# pecoskiSmartWatch-BASIC-TOP.net
KiCad netlist of a schematic drawn in EAGLE
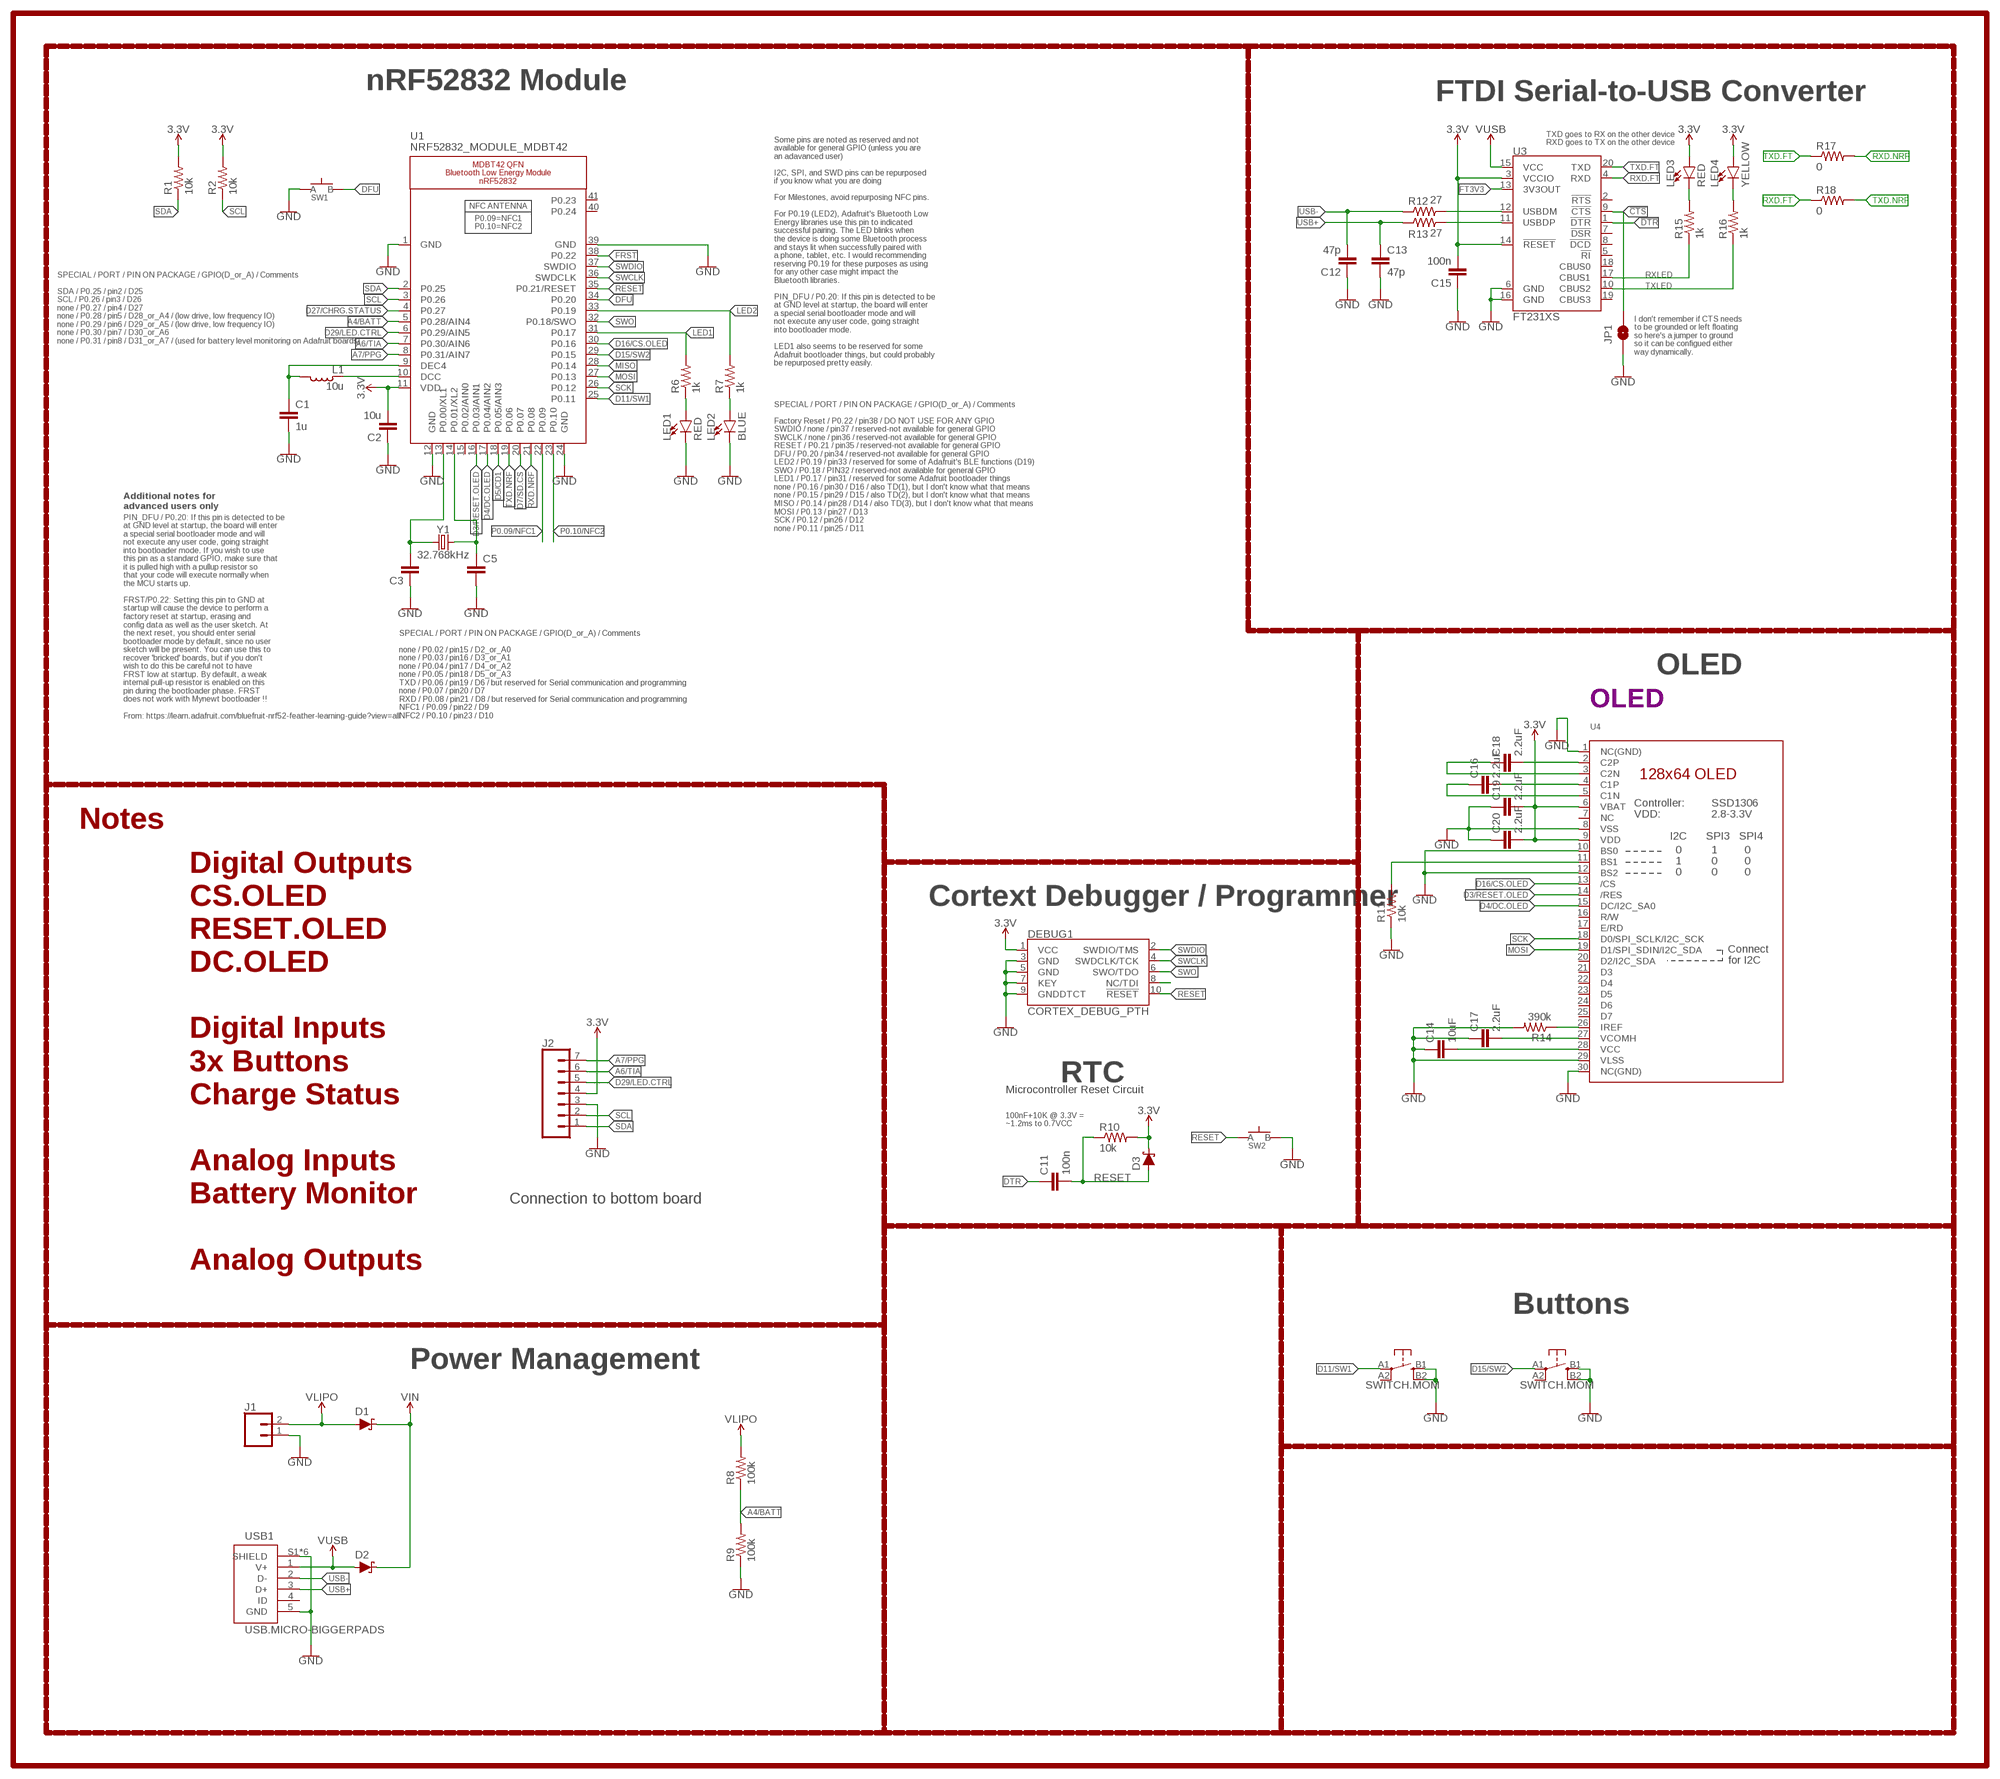
[diagram p0: schematic, sheet 1]

(export (version "E")
  (design (tool "Eeschema 10.0.6"))
  (components
    (comp (ref "C1")
      (value "1u")
      (footprint "eagle-import:C0603")
      (libsource (lib "eagle-import") (part "CAPACITOR0603"))
    )
    (comp (ref "C2")
      (value "10u")
      (footprint "eagle-import:C0805")
      (libsource (lib "eagle-import") (part "CAPACITOR0805"))
    )
    (comp (ref "C3")
      (value "CAPACITOR0603")
      (footprint "eagle-import:C0603")
      (libsource (lib "eagle-import") (part "CAPACITOR0603"))
    )
    (comp (ref "C5")
      (value "CAPACITOR0603")
      (footprint "eagle-import:C0603")
      (libsource (lib "eagle-import") (part "CAPACITOR0603"))
    )
    (comp (ref "C11")
      (value "100n")
      (footprint "eagle-import:C0603")
      (libsource (lib "eagle-import") (part "CAPACITOR0603"))
    )
    (comp (ref "C12")
      (value "47p")
      (footprint "eagle-import:C0603")
      (libsource (lib "eagle-import") (part "CAPACITOR0603"))
    )
    (comp (ref "C13")
      (value "47p")
      (footprint "eagle-import:C0603")
      (libsource (lib "eagle-import") (part "CAPACITOR0603"))
    )
    (comp (ref "C14")
      (value "10uF")
      (footprint "eagle-import:C0603")
      (libsource (lib "eagle-import") (part "CAPACITOR0603"))
    )
    (comp (ref "C15")
      (value "100n")
      (footprint "eagle-import:C0603")
      (libsource (lib "eagle-import") (part "CAPACITOR0603"))
    )
    (comp (ref "C16")
      (value "2.2uF")
      (footprint "eagle-import:C0402")
      (libsource (lib "eagle-import") (part "CAPACITOR0402"))
    )
    (comp (ref "C17")
      (value "2.2uF")
      (footprint "eagle-import:C0402")
      (libsource (lib "eagle-import") (part "CAPACITOR0402"))
    )
    (comp (ref "C18")
      (value "2.2uF")
      (footprint "eagle-import:C0402")
      (libsource (lib "eagle-import") (part "CAPACITOR0402"))
    )
    (comp (ref "C19")
      (value "2.2uF")
      (footprint "eagle-import:C0402")
      (libsource (lib "eagle-import") (part "CAPACITOR0402"))
    )
    (comp (ref "C20")
      (value "2.2uF")
      (footprint "eagle-import:C0402")
      (libsource (lib "eagle-import") (part "CAPACITOR0402"))
    )
    (comp (ref "D1")
      (value "SCHOTTKY-USC")
      (footprint "eagle-import:USC")
      (libsource (lib "eagle-import") (part "SCHOTTKY-USC"))
    )
    (comp (ref "D2")
      (value "SCHOTTKY-USC")
      (footprint "eagle-import:USC")
      (libsource (lib "eagle-import") (part "SCHOTTKY-USC"))
    )
    (comp (ref "D3")
      (value "SCHOTTKY-USC")
      (footprint "eagle-import:USC")
      (libsource (lib "eagle-import") (part "SCHOTTKY-USC"))
    )
    (comp (ref "DEBUG1")
      (value "CORTEX_DEBUG_PTH")
      (footprint "eagle-import:2X5-PTH-1.27MM")
      (libsource (lib "eagle-import") (part "CORTEX_DEBUG_PTH"))
    )
    (comp (ref "J1")
      (value "CONN_02")
      (footprint "eagle-import:1X02")
      (libsource (lib "eagle-import") (part "CONN_02"))
    )
    (comp (ref "J2")
      (value "CONN_07-1.27MM")
      (footprint "eagle-import:1X07_1.27MM")
      (libsource (lib "eagle-import") (part "CONN_07-1.27MM"))
    )
    (comp (ref "JP1")
      (value "JUMPER-SMT_2_NO_SILK")
      (footprint "eagle-import:SMT-JUMPER_2_NO_SILK")
      (libsource (lib "eagle-import") (part "JUMPER-SMT_2_NO_SILK"))
    )
    (comp (ref "L1")
      (value "10u")
      (footprint "eagle-import:L0603")
      (libsource (lib "eagle-import") (part "INDUCTOR0603"))
    )
    (comp (ref "LED1")
      (value "RED")
      (footprint "eagle-import:LED-0603")
      (libsource (lib "eagle-import") (part "LED0603"))
    )
    (comp (ref "LED2")
      (value "BLUE")
      (footprint "eagle-import:LED-0603")
      (libsource (lib "eagle-import") (part "LED0603"))
    )
    (comp (ref "LED3")
      (value "RED")
      (footprint "eagle-import:LED-0603")
      (libsource (lib "eagle-import") (part "LED0603"))
    )
    (comp (ref "LED4")
      (value "YELLOW")
      (footprint "eagle-import:LED-0603")
      (libsource (lib "eagle-import") (part "LED0603"))
    )
    (comp (ref "R1")
      (value "10k")
      (footprint "eagle-import:R0603")
      (libsource (lib "eagle-import") (part "RESISTOR0603"))
    )
    (comp (ref "R2")
      (value "10k")
      (footprint "eagle-import:R0603")
      (libsource (lib "eagle-import") (part "RESISTOR0603"))
    )
    (comp (ref "R6")
      (value "1k")
      (footprint "eagle-import:R0603")
      (libsource (lib "eagle-import") (part "RESISTOR0603"))
    )
    (comp (ref "R7")
      (value "1k")
      (footprint "eagle-import:R0603")
      (libsource (lib "eagle-import") (part "RESISTOR0603"))
    )
    (comp (ref "R8")
      (value "100k")
      (footprint "eagle-import:R0603")
      (libsource (lib "eagle-import") (part "RESISTOR0603"))
    )
    (comp (ref "R9")
      (value "100k")
      (footprint "eagle-import:R0603")
      (libsource (lib "eagle-import") (part "RESISTOR0603"))
    )
    (comp (ref "R10")
      (value "10k")
      (footprint "eagle-import:R0603")
      (libsource (lib "eagle-import") (part "RESISTOR0603"))
    )
    (comp (ref "R11")
      (value "10k")
      (footprint "eagle-import:R0603")
      (libsource (lib "eagle-import") (part "RESISTOR0603"))
    )
    (comp (ref "R12")
      (value "27")
      (footprint "eagle-import:R0603")
      (libsource (lib "eagle-import") (part "RESISTOR0603"))
    )
    (comp (ref "R13")
      (value "27")
      (footprint "eagle-import:R0603")
      (libsource (lib "eagle-import") (part "RESISTOR0603"))
    )
    (comp (ref "R14")
      (value "390k")
      (footprint "eagle-import:R0603")
      (libsource (lib "eagle-import") (part "RESISTOR0603"))
    )
    (comp (ref "R15")
      (value "1k")
      (footprint "eagle-import:R0603")
      (libsource (lib "eagle-import") (part "RESISTOR0603"))
    )
    (comp (ref "R16")
      (value "1k")
      (footprint "eagle-import:R0603")
      (libsource (lib "eagle-import") (part "RESISTOR0603"))
    )
    (comp (ref "R17")
      (value "0")
      (footprint "eagle-import:R0603")
      (libsource (lib "eagle-import") (part "RESISTOR0603"))
    )
    (comp (ref "R18")
      (value "0")
      (footprint "eagle-import:R0603")
      (libsource (lib "eagle-import") (part "RESISTOR0603"))
    )
    (comp (ref "SW1")
      (value "SPST-PTS830GG140-COPY.1-3")
      (footprint "eagle-import:BUTTON-GULLWING")
      (libsource (lib "eagle-import") (part "SPST-PTS830GG140-COPY.1-3"))
    )
    (comp (ref "SW2")
      (value "SPST-PTS830GG140-COPY.1-3")
      (footprint "eagle-import:BUTTON-GULLWING")
      (libsource (lib "eagle-import") (part "SPST-PTS830GG140-COPY.1-3"))
    )
    (comp (ref "SW3")
      (value "SWITCH.MOM")
      (footprint "eagle-import:TACTILE_SWITCH_SMD_6.2MM_TALL")
      (libsource (lib "eagle-import") (part "SWITCH.MOM"))
    )
    (comp (ref "SW4")
      (value "SWITCH.MOM")
      (footprint "eagle-import:TACTILE_SWITCH_SMD_6.2MM_TALL")
      (libsource (lib "eagle-import") (part "SWITCH.MOM"))
    )
    (comp (ref "U1")
      (value "NRF52832_MODULE_MDBT42")
      (footprint "eagle-import:BLE_MODULE_RAYTAC_MDBT42")
      (libsource (lib "eagle-import") (part "NRF52832_MODULE_MDBT42"))
    )
    (comp (ref "U3")
      (value "FT231XS")
      (footprint "eagle-import:SSOP20_L")
      (libsource (lib "eagle-import") (part "FT231XS"))
    )
    (comp (ref "U4")
      (value "DISP_OLED_UG-2864HSWEG01-NO-WRAPAROUND")
      (footprint "eagle-import:UG-2864HSWEG01_0.96IN_NO-WRAPAROUND")
      (libsource (lib "eagle-import") (part "DISP_OLED_UG-2864HSWEG01-NO-WRAPAROUND"))
    )
    (comp (ref "USB1")
      (value "USB.MICRO-BIGGERPADS")
      (footprint "eagle-import:USB-MICRO-01.BIGGERPADS")
      (libsource (lib "eagle-import") (part "USB.MICRO-BIGGERPADS"))
    )
    (comp (ref "Y1")
      (value "32.768kHz")
      (footprint "eagle-import:2-SMD.NOLEAD.2.0MMTO1.2MM")
      (libsource (lib "eagle-import") (part "CRYSTALECS-.327-12.5-12-C-TR"))
    )
  )
  (nets
    (net (code "1") (name "/RXLED") (class "Default")
      (node (ref "R15") (pin "1") (pinfunction "1_1") (pintype "passive"))
      (node (ref "U3") (pin "17") (pinfunction "CBUS1_17") (pintype "bidirectional"))
    )
    (net (code "2") (name "/TXLED") (class "Default")
      (node (ref "R16") (pin "1") (pinfunction "1_1") (pintype "passive"))
      (node (ref "U3") (pin "10") (pinfunction "CBUS2_10") (pintype "bidirectional"))
    )
    (net (code "3") (name "/~{CTS}") (class "Default")
      (node (ref "JP1") (pin "2") (pinfunction "2_2") (pintype "passive"))
      (node (ref "U3") (pin "9") (pinfunction "~{CTS}_9") (pintype "bidirectional"))
    )
    (net (code "4") (name "/~{DTR}") (class "Default")
      (node (ref "U3") (pin "1") (pinfunction "~{DTR}_1") (pintype "bidirectional"))
    )
    (net (code "5") (name "3.3V") (class "Default")
      (node (ref "C15") (pin "2") (pinfunction "2_2") (pintype "passive"))
      (node (ref "C19") (pin "2") (pinfunction "2_2") (pintype "passive"))
      (node (ref "C2") (pin "2") (pinfunction "2_2") (pintype "passive"))
      (node (ref "C20") (pin "2") (pinfunction "2_2") (pintype "passive"))
      (node (ref "D3") (pin "-") (pinfunction "C_-") (pintype "passive"))
      (node (ref "DEBUG1") (pin "1") (pinfunction "VCC_1") (pintype "bidirectional"))
      (node (ref "J2") (pin "4") (pinfunction "4_4") (pintype "passive"))
      (node (ref "LED3") (pin "A") (pinfunction "A_A") (pintype "passive"))
      (node (ref "LED4") (pin "A") (pinfunction "A_A") (pintype "passive"))
      (node (ref "R1") (pin "2") (pinfunction "2_2") (pintype "passive"))
      (node (ref "R10") (pin "2") (pinfunction "2_2") (pintype "passive"))
      (node (ref "R2") (pin "2") (pinfunction "2_2") (pintype "passive"))
      (node (ref "U1") (pin "11") (pinfunction "VDD_11") (pintype "bidirectional"))
      (node (ref "U3") (pin "14") (pinfunction "~{RESET}_14") (pintype "bidirectional"))
      (node (ref "U3") (pin "3") (pinfunction "VCCIO_3") (pintype "bidirectional"))
      (node (ref "U4") (pin "6") (pinfunction "VBAT_6") (pintype "input"))
      (node (ref "U4") (pin "9") (pinfunction "VDD_9") (pintype "power_in"))
    )
    (net (code "6") (name "A4{slash}BATT") (class "Default")
      (node (ref "R8") (pin "1") (pinfunction "1_1") (pintype "passive"))
      (node (ref "R9") (pin "2") (pinfunction "2_2") (pintype "passive"))
      (node (ref "U1") (pin "5") (pinfunction "P0.28/AIN4_5") (pintype "bidirectional"))
    )
    (net (code "7") (name "A6{slash}TIA") (class "Default")
      (node (ref "J2") (pin "6") (pinfunction "6_6") (pintype "passive"))
      (node (ref "U1") (pin "7") (pinfunction "P0.30/AIN6_7") (pintype "bidirectional"))
    )
    (net (code "8") (name "A7{slash}PPG") (class "Default")
      (node (ref "J2") (pin "7") (pinfunction "7_7") (pintype "passive"))
      (node (ref "U1") (pin "8") (pinfunction "P0.31/AIN7_8") (pintype "bidirectional"))
    )
    (net (code "9") (name "D3{slash}RESET.OLED") (class "Default")
      (node (ref "U1") (pin "16") (pinfunction "P0.03/AIN1_16") (pintype "bidirectional"))
      (node (ref "U4") (pin "14") (pinfunction "/RES_14") (pintype "input"))
    )
    (net (code "10") (name "D4{slash}DC.OLED") (class "Default")
      (node (ref "U1") (pin "17") (pinfunction "P0.04/AIN2_17") (pintype "bidirectional"))
      (node (ref "U4") (pin "15") (pinfunction "DC/I2C_SA0_15") (pintype "input"))
    )
    (net (code "11") (name "D5{slash}CD1") (class "Default")
      (node (ref "U1") (pin "18") (pinfunction "P0.05/AIN3_18") (pintype "bidirectional"))
    )
    (net (code "12") (name "D7{slash}SD.CS") (class "Default")
      (node (ref "U1") (pin "20") (pinfunction "P0.07_20") (pintype "bidirectional"))
    )
    (net (code "13") (name "D11{slash}SW1") (class "Default")
      (node (ref "SW3") (pin "A1") (pinfunction "1_A1") (pintype "passive"))
      (node (ref "U1") (pin "25") (pinfunction "P0.11_25") (pintype "bidirectional"))
    )
    (net (code "14") (name "D15{slash}SW2") (class "Default")
      (node (ref "SW4") (pin "A1") (pinfunction "1_A1") (pintype "passive"))
      (node (ref "U1") (pin "29") (pinfunction "P0.15_29") (pintype "bidirectional"))
    )
    (net (code "15") (name "D16{slash}CS.OLED") (class "Default")
      (node (ref "U1") (pin "30") (pinfunction "P0.16_30") (pintype "bidirectional"))
      (node (ref "U4") (pin "13") (pinfunction "/CS_13") (pintype "input"))
    )
    (net (code "16") (name "D27{slash}CHRG.STATUS") (class "Default")
      (node (ref "U1") (pin "4") (pinfunction "P0.27_4") (pintype "bidirectional"))
    )
    (net (code "17") (name "D29{slash}LED.CTRL") (class "Default")
      (node (ref "J2") (pin "5") (pinfunction "5_5") (pintype "passive"))
      (node (ref "U1") (pin "6") (pinfunction "P0.29/AIN5_6") (pintype "bidirectional"))
    )
    (net (code "18") (name "DFU") (class "Default")
      (node (ref "SW1") (pin "3") (pinfunction "B_3") (pintype "bidirectional"))
      (node (ref "U1") (pin "34") (pinfunction "P0.20_34") (pintype "bidirectional"))
    )
    (net (code "19") (name "DTR") (class "Default")
      (node (ref "C11") (pin "1") (pinfunction "1_1") (pintype "passive"))
    )
    (net (code "20") (name "FRST") (class "Default")
      (node (ref "U1") (pin "38") (pinfunction "P0.22_38") (pintype "bidirectional"))
    )
    (net (code "21") (name "FT3V3") (class "Default")
      (node (ref "U3") (pin "13") (pinfunction "3V3OUT_13") (pintype "bidirectional"))
    )
    (net (code "22") (name "GND") (class "Default")
      (node (ref "C1") (pin "2") (pinfunction "2_2") (pintype "passive"))
      (node (ref "C12") (pin "1") (pinfunction "1_1") (pintype "passive"))
      (node (ref "C13") (pin "2") (pinfunction "2_2") (pintype "passive"))
      (node (ref "C14") (pin "1") (pinfunction "1_1") (pintype "passive"))
      (node (ref "C15") (pin "1") (pinfunction "1_1") (pintype "passive"))
      (node (ref "C17") (pin "1") (pinfunction "1_1") (pintype "passive"))
      (node (ref "C19") (pin "1") (pinfunction "1_1") (pintype "passive"))
      (node (ref "C2") (pin "1") (pinfunction "1_1") (pintype "passive"))
      (node (ref "C20") (pin "1") (pinfunction "1_1") (pintype "passive"))
      (node (ref "C3") (pin "1") (pinfunction "1_1") (pintype "passive"))
      (node (ref "C5") (pin "2") (pinfunction "2_2") (pintype "passive"))
      (node (ref "DEBUG1") (pin "3") (pinfunction "GND_3") (pintype "bidirectional"))
      (node (ref "DEBUG1") (pin "5") (pinfunction "GND_5") (pintype "bidirectional"))
      (node (ref "DEBUG1") (pin "7") (pinfunction "KEY_7") (pintype "bidirectional"))
      (node (ref "DEBUG1") (pin "9") (pinfunction "GNDDTCT_9") (pintype "bidirectional"))
      (node (ref "J1") (pin "1") (pinfunction "1_1") (pintype "passive"))
      (node (ref "J2") (pin "3") (pinfunction "3_3") (pintype "passive"))
      (node (ref "JP1") (pin "1") (pinfunction "1_1") (pintype "passive"))
      (node (ref "LED1") (pin "C") (pinfunction "C_C") (pintype "passive"))
      (node (ref "LED2") (pin "C") (pinfunction "C_C") (pintype "passive"))
      (node (ref "R11") (pin "1") (pinfunction "1_1") (pintype "passive"))
      (node (ref "R14") (pin "2") (pinfunction "2_2") (pintype "passive"))
      (node (ref "R9") (pin "1") (pinfunction "1_1") (pintype "passive"))
      (node (ref "SW1") (pin "1") (pinfunction "A_1") (pintype "bidirectional"))
      (node (ref "SW2") (pin "3") (pinfunction "B_3") (pintype "bidirectional"))
      (node (ref "SW3") (pin "B1") (pinfunction "3_B1") (pintype "passive"))
      (node (ref "SW3") (pin "B2") (pinfunction "4_B2") (pintype "passive"))
      (node (ref "SW4") (pin "B1") (pinfunction "3_B1") (pintype "passive"))
      (node (ref "SW4") (pin "B2") (pinfunction "4_B2") (pintype "passive"))
      (node (ref "U1") (pin "1") (pinfunction "GND_1") (pintype "bidirectional"))
      (node (ref "U1") (pin "12") (pinfunction "GND_12") (pintype "bidirectional"))
      (node (ref "U1") (pin "24") (pinfunction "GND_24") (pintype "bidirectional"))
      (node (ref "U1") (pin "39") (pinfunction "GND_39") (pintype "bidirectional"))
      (node (ref "U3") (pin "16") (pinfunction "GND_16") (pintype "bidirectional"))
      (node (ref "U3") (pin "6") (pinfunction "GND_6") (pintype "bidirectional"))
      (node (ref "U4") (pin "1") (pinfunction "NC(GND)_1") (pintype "input"))
      (node (ref "U4") (pin "10") (pinfunction "BS0_10") (pintype "input"))
      (node (ref "U4") (pin "12") (pinfunction "BS2_12") (pintype "input"))
      (node (ref "U4") (pin "29") (pinfunction "VLSS_29") (pintype "power_in"))
      (node (ref "U4") (pin "30") (pinfunction "NC(GND)_30") (pintype "input"))
      (node (ref "U4") (pin "8") (pinfunction "VSS_8") (pintype "power_in"))
      (node (ref "USB1") (pin "5") (pinfunction "GND_5") (pintype "bidirectional"))
      (node (ref "USB1") (pin "S1") (pinfunction "SHIELD_S1") (pintype "bidirectional"))
      (node (ref "USB1") (pin "S2") (pinfunction "SHIELD_S2") (pintype "bidirectional"))
      (node (ref "USB1") (pin "S3") (pinfunction "SHIELD_S3") (pintype "bidirectional"))
      (node (ref "USB1") (pin "S4") (pinfunction "SHIELD_S4") (pintype "bidirectional"))
      (node (ref "USB1") (pin "S5") (pinfunction "SHIELD_S5") (pintype "bidirectional"))
      (node (ref "USB1") (pin "S6") (pinfunction "SHIELD_S6") (pintype "bidirectional"))
    )
    (net (code "23") (name "LED1") (class "Default")
      (node (ref "R6") (pin "2") (pinfunction "2_2") (pintype "passive"))
      (node (ref "U1") (pin "31") (pinfunction "P0.17_31") (pintype "bidirectional"))
    )
    (net (code "24") (name "LED2") (class "Default")
      (node (ref "R7") (pin "2") (pinfunction "2_2") (pintype "passive"))
      (node (ref "U1") (pin "33") (pinfunction "P0.19_33") (pintype "bidirectional"))
    )
    (net (code "25") (name "MISO") (class "Default")
      (node (ref "U1") (pin "28") (pinfunction "P0.14_28") (pintype "bidirectional"))
    )
    (net (code "26") (name "MOSI") (class "Default")
      (node (ref "U1") (pin "27") (pinfunction "P0.13_27") (pintype "bidirectional"))
      (node (ref "U4") (pin "19") (pinfunction "D1/SPI_SDIN/I2C_SDA_19") (pintype "bidirectional"))
    )
    (net (code "27") (name "Net-(LED1-PadA)") (class "Default")
      (node (ref "LED1") (pin "A") (pinfunction "A_A") (pintype "passive"))
      (node (ref "R6") (pin "1") (pinfunction "1_1") (pintype "passive"))
    )
    (net (code "28") (name "Net-(LED2-PadA)") (class "Default")
      (node (ref "LED2") (pin "A") (pinfunction "A_A") (pintype "passive"))
      (node (ref "R7") (pin "1") (pinfunction "1_1") (pintype "passive"))
    )
    (net (code "29") (name "Net-(LED3-PadC)") (class "Default")
      (node (ref "LED3") (pin "C") (pinfunction "C_C") (pintype "passive"))
      (node (ref "R15") (pin "2") (pinfunction "2_2") (pintype "passive"))
    )
    (net (code "30") (name "Net-(LED4-PadC)") (class "Default")
      (node (ref "LED4") (pin "C") (pinfunction "C_C") (pintype "passive"))
      (node (ref "R16") (pin "2") (pinfunction "2_2") (pintype "passive"))
    )
    (net (code "31") (name "Net-(U1-DCC)") (class "Default")
      (node (ref "L1") (pin "1") (pinfunction "1_1") (pintype "passive"))
      (node (ref "U1") (pin "10") (pinfunction "DCC_10") (pintype "bidirectional"))
    )
    (net (code "32") (name "Net-(U1-DEC4)") (class "Default")
      (node (ref "C1") (pin "1") (pinfunction "1_1") (pintype "passive"))
      (node (ref "L1") (pin "2") (pinfunction "2_2") (pintype "passive"))
      (node (ref "U1") (pin "9") (pinfunction "DEC4_9") (pintype "bidirectional"))
    )
    (net (code "33") (name "Net-(U1-P0.00{slash}XL1)") (class "Default")
      (node (ref "C3") (pin "2") (pinfunction "2_2") (pintype "passive"))
      (node (ref "U1") (pin "13") (pinfunction "P0.00/XL1_13") (pintype "bidirectional"))
      (node (ref "Y1") (pin "P$1") (pinfunction "1_P$1") (pintype "passive"))
    )
    (net (code "34") (name "Net-(U1-P0.01{slash}XL2)") (class "Default")
      (node (ref "C5") (pin "1") (pinfunction "1_1") (pintype "passive"))
      (node (ref "U1") (pin "14") (pinfunction "P0.01/XL2_14") (pintype "bidirectional"))
      (node (ref "Y1") (pin "P$2") (pinfunction "2_P$2") (pintype "passive"))
    )
    (net (code "35") (name "Net-(U3-USBDM)") (class "Default")
      (node (ref "R12") (pin "2") (pinfunction "2_2") (pintype "passive"))
      (node (ref "U3") (pin "12") (pinfunction "USBDM_12") (pintype "bidirectional"))
    )
    (net (code "36") (name "Net-(U3-USBDP)") (class "Default")
      (node (ref "R13") (pin "2") (pinfunction "2_2") (pintype "passive"))
      (node (ref "U3") (pin "11") (pinfunction "USBDP_11") (pintype "bidirectional"))
    )
    (net (code "37") (name "Net-(U4-BS1)") (class "Default")
      (node (ref "R11") (pin "2") (pinfunction "2_2") (pintype "passive"))
      (node (ref "U4") (pin "11") (pinfunction "BS1_11") (pintype "input"))
    )
    (net (code "38") (name "Net-(U4-C1N)") (class "Default")
      (node (ref "C16") (pin "1") (pinfunction "1_1") (pintype "passive"))
      (node (ref "U4") (pin "5") (pinfunction "C1N_5") (pintype "input"))
    )
    (net (code "39") (name "Net-(U4-C1P)") (class "Default")
      (node (ref "C16") (pin "2") (pinfunction "2_2") (pintype "passive"))
      (node (ref "U4") (pin "4") (pinfunction "C1P_4") (pintype "input"))
    )
    (net (code "40") (name "Net-(U4-C2N)") (class "Default")
      (node (ref "C18") (pin "1") (pinfunction "1_1") (pintype "passive"))
      (node (ref "U4") (pin "3") (pinfunction "C2N_3") (pintype "input"))
    )
    (net (code "41") (name "Net-(U4-C2P)") (class "Default")
      (node (ref "C18") (pin "2") (pinfunction "2_2") (pintype "passive"))
      (node (ref "U4") (pin "2") (pinfunction "C2P_2") (pintype "input"))
    )
    (net (code "42") (name "Net-(U4-IREF)") (class "Default")
      (node (ref "R14") (pin "1") (pinfunction "1_1") (pintype "passive"))
      (node (ref "U4") (pin "26") (pinfunction "IREF_26") (pintype "input"))
    )
    (net (code "43") (name "Net-(U4-VCC)") (class "Default")
      (node (ref "C14") (pin "2") (pinfunction "2_2") (pintype "passive"))
      (node (ref "U4") (pin "28") (pinfunction "VCC_28") (pintype "power_in"))
    )
    (net (code "44") (name "Net-(U4-VCOMH)") (class "Default")
      (node (ref "C17") (pin "2") (pinfunction "2_2") (pintype "passive"))
      (node (ref "U4") (pin "27") (pinfunction "VCOMH_27") (pintype "output"))
    )
    (net (code "45") (name "P0.09{slash}NFC1") (class "Default")
      (node (ref "U1") (pin "22") (pinfunction "P0.09_22") (pintype "bidirectional"))
    )
    (net (code "46") (name "P0.10{slash}NFC2") (class "Default")
      (node (ref "U1") (pin "23") (pinfunction "P0.10_23") (pintype "bidirectional"))
    )
    (net (code "47") (name "RESET") (class "Default")
      (node (ref "C11") (pin "2") (pinfunction "2_2") (pintype "passive"))
      (node (ref "D3") (pin "+") (pinfunction "A_+") (pintype "passive"))
      (node (ref "DEBUG1") (pin "10") (pinfunction "~{RESET}_10") (pintype "bidirectional"))
      (node (ref "R10") (pin "1") (pinfunction "1_1") (pintype "passive"))
      (node (ref "SW2") (pin "1") (pinfunction "A_1") (pintype "bidirectional"))
      (node (ref "U1") (pin "35") (pinfunction "P0.21/RESET_35") (pintype "bidirectional"))
    )
    (net (code "48") (name "RXD.FT") (class "Default")
      (node (ref "R18") (pin "1") (pinfunction "1_1") (pintype "passive"))
      (node (ref "U3") (pin "4") (pinfunction "RXD_4") (pintype "bidirectional"))
    )
    (net (code "49") (name "RXD.NRF") (class "Default")
      (node (ref "R17") (pin "2") (pinfunction "2_2") (pintype "passive"))
      (node (ref "U1") (pin "21") (pinfunction "P0.08_21") (pintype "bidirectional"))
    )
    (net (code "50") (name "SCK") (class "Default")
      (node (ref "U1") (pin "26") (pinfunction "P0.12_26") (pintype "bidirectional"))
      (node (ref "U4") (pin "18") (pinfunction "D0/SPI_SCLK/I2C_SCK_18") (pintype "bidirectional"))
    )
    (net (code "51") (name "SCL") (class "Default")
      (node (ref "J2") (pin "2") (pinfunction "2_2") (pintype "passive"))
      (node (ref "R2") (pin "1") (pinfunction "1_1") (pintype "passive"))
      (node (ref "U1") (pin "3") (pinfunction "P0.26_3") (pintype "bidirectional"))
    )
    (net (code "52") (name "SDA") (class "Default")
      (node (ref "J2") (pin "1") (pinfunction "1_1") (pintype "passive"))
      (node (ref "R1") (pin "1") (pinfunction "1_1") (pintype "passive"))
      (node (ref "U1") (pin "2") (pinfunction "P0.25_2") (pintype "bidirectional"))
    )
    (net (code "53") (name "SWCLK") (class "Default")
      (node (ref "DEBUG1") (pin "4") (pinfunction "SWDCLK/TCK_4") (pintype "bidirectional"))
      (node (ref "U1") (pin "36") (pinfunction "SWDCLK_36") (pintype "bidirectional"))
    )
    (net (code "54") (name "SWDIO") (class "Default")
      (node (ref "DEBUG1") (pin "2") (pinfunction "SWDIO/TMS_2") (pintype "bidirectional"))
      (node (ref "U1") (pin "37") (pinfunction "SWDIO_37") (pintype "bidirectional"))
    )
    (net (code "55") (name "SWO") (class "Default")
      (node (ref "DEBUG1") (pin "6") (pinfunction "SWO/TDO_6") (pintype "bidirectional"))
      (node (ref "U1") (pin "32") (pinfunction "P0.18/SWO_32") (pintype "bidirectional"))
    )
    (net (code "56") (name "TXD.FT") (class "Default")
      (node (ref "R17") (pin "1") (pinfunction "1_1") (pintype "passive"))
      (node (ref "U3") (pin "20") (pinfunction "TXD_20") (pintype "bidirectional"))
    )
    (net (code "57") (name "TXD.NRF") (class "Default")
      (node (ref "R18") (pin "2") (pinfunction "2_2") (pintype "passive"))
      (node (ref "U1") (pin "19") (pinfunction "P0.06_19") (pintype "bidirectional"))
    )
    (net (code "58") (name "USB+") (class "Default")
      (node (ref "C13") (pin "1") (pinfunction "1_1") (pintype "passive"))
      (node (ref "R13") (pin "1") (pinfunction "1_1") (pintype "passive"))
      (node (ref "USB1") (pin "3") (pinfunction "D+_3") (pintype "bidirectional"))
    )
    (net (code "59") (name "USB-") (class "Default")
      (node (ref "C12") (pin "2") (pinfunction "2_2") (pintype "passive"))
      (node (ref "R12") (pin "1") (pinfunction "1_1") (pintype "passive"))
      (node (ref "USB1") (pin "2") (pinfunction "D-_2") (pintype "bidirectional"))
    )
    (net (code "60") (name "VIN") (class "Default")
      (node (ref "D1") (pin "-") (pinfunction "C_-") (pintype "passive"))
      (node (ref "D2") (pin "-") (pinfunction "C_-") (pintype "passive"))
    )
    (net (code "61") (name "VLIPO") (class "Default")
      (node (ref "D1") (pin "+") (pinfunction "A_+") (pintype "passive"))
      (node (ref "J1") (pin "2") (pinfunction "2_2") (pintype "passive"))
      (node (ref "R8") (pin "2") (pinfunction "2_2") (pintype "passive"))
    )
    (net (code "62") (name "VUSB") (class "Default")
      (node (ref "D2") (pin "+") (pinfunction "A_+") (pintype "passive"))
      (node (ref "U3") (pin "15") (pinfunction "VCC_15") (pintype "bidirectional"))
      (node (ref "USB1") (pin "1") (pinfunction "V+_1") (pintype "bidirectional"))
    )
    (net (code "63") (name "unconnected-(DEBUG1-NC{slash}TDI-Pad8)") (class "Default")
      (node (ref "DEBUG1") (pin "8") (pinfunction "NC/TDI_8") (pintype "bidirectional"))
    )
    (net (code "64") (name "unconnected-(SW3-2-PadA2)") (class "Default")
      (node (ref "SW3") (pin "A2") (pinfunction "2_A2") (pintype "passive"))
    )
    (net (code "65") (name "unconnected-(SW4-2-PadA2)") (class "Default")
      (node (ref "SW4") (pin "A2") (pinfunction "2_A2") (pintype "passive"))
    )
    (net (code "66") (name "unconnected-(U1-P0.02{slash}AIN0-Pad15)") (class "Default")
      (node (ref "U1") (pin "15") (pinfunction "P0.02/AIN0_15") (pintype "bidirectional"))
    )
    (net (code "67") (name "unconnected-(U1-P0.23-Pad41)") (class "Default")
      (node (ref "U1") (pin "41") (pinfunction "P0.23_41") (pintype "bidirectional"))
    )
    (net (code "68") (name "unconnected-(U1-P0.24-Pad40)") (class "Default")
      (node (ref "U1") (pin "40") (pinfunction "P0.24_40") (pintype "bidirectional"))
    )
    (net (code "69") (name "unconnected-(U3-CBUS0-Pad18)") (class "Default")
      (node (ref "U3") (pin "18") (pinfunction "CBUS0_18") (pintype "bidirectional"))
    )
    (net (code "70") (name "unconnected-(U3-CBUS3-Pad19)") (class "Default")
      (node (ref "U3") (pin "19") (pinfunction "CBUS3_19") (pintype "bidirectional"))
    )
    (net (code "71") (name "unconnected-(U3-~{DCD}-Pad8)") (class "Default")
      (node (ref "U3") (pin "8") (pinfunction "~{DCD}_8") (pintype "bidirectional"))
    )
    (net (code "72") (name "unconnected-(U3-~{DSR}-Pad7)") (class "Default")
      (node (ref "U3") (pin "7") (pinfunction "~{DSR}_7") (pintype "bidirectional"))
    )
    (net (code "73") (name "unconnected-(U3-~{RI}-Pad5)") (class "Default")
      (node (ref "U3") (pin "5") (pinfunction "~{RI}_5") (pintype "bidirectional"))
    )
    (net (code "74") (name "unconnected-(U3-~{RTS}-Pad2)") (class "Default")
      (node (ref "U3") (pin "2") (pinfunction "~{RTS}_2") (pintype "bidirectional"))
    )
    (net (code "75") (name "unconnected-(U4-D2{slash}I2C_SDA-Pad20)") (class "Default")
      (node (ref "U4") (pin "20") (pinfunction "D2/I2C_SDA_20") (pintype "bidirectional"))
    )
    (net (code "76") (name "unconnected-(U4-D3-Pad21)") (class "Default")
      (node (ref "U4") (pin "21") (pinfunction "D3_21") (pintype "bidirectional"))
    )
    (net (code "77") (name "unconnected-(U4-D4-Pad22)") (class "Default")
      (node (ref "U4") (pin "22") (pinfunction "D4_22") (pintype "bidirectional"))
    )
    (net (code "78") (name "unconnected-(U4-D5-Pad23)") (class "Default")
      (node (ref "U4") (pin "23") (pinfunction "D5_23") (pintype "bidirectional"))
    )
    (net (code "79") (name "unconnected-(U4-D6-Pad24)") (class "Default")
      (node (ref "U4") (pin "24") (pinfunction "D6_24") (pintype "bidirectional"))
    )
    (net (code "80") (name "unconnected-(U4-D7-Pad25)") (class "Default")
      (node (ref "U4") (pin "25") (pinfunction "D7_25") (pintype "bidirectional"))
    )
    (net (code "81") (name "unconnected-(U4-E{slash}RD-Pad17)") (class "Default")
      (node (ref "U4") (pin "17") (pinfunction "E/RD_17") (pintype "input"))
    )
    (net (code "82") (name "unconnected-(U4-NC-Pad7)") (class "Default")
      (node (ref "U4") (pin "7") (pinfunction "NC_7") (pintype "no_connect"))
    )
    (net (code "83") (name "unconnected-(U4-R{slash}W-Pad16)") (class "Default")
      (node (ref "U4") (pin "16") (pinfunction "R/W_16") (pintype "input"))
    )
    (net (code "84") (name "unconnected-(USB1-ID-Pad4)") (class "Default")
      (node (ref "USB1") (pin "4") (pinfunction "ID_4") (pintype "bidirectional"))
    )
  )
)
